# opk-pi-1wire-i2c-v1.net
KiCad netlist of a schematic drawn in EAGLE
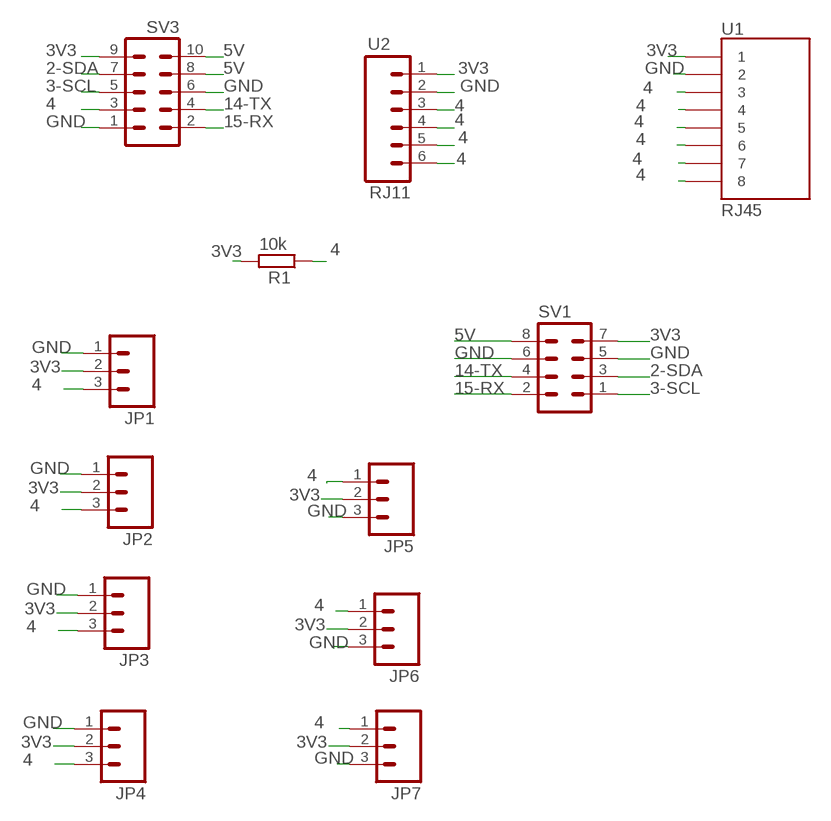
[diagram p0: schematic, sheet 1]

(export (version "E")
  (design (tool "Eeschema 10.0.6"))
  (components
    (comp (ref "JP1")
      (value "M03SCREW")
      (footprint "eagle-import:SCREWTERMINAL-3.5MM-3")
      (libsource (lib "eagle-import") (part "M03SCREW"))
    )
    (comp (ref "JP2")
      (value "M03SCREW")
      (footprint "eagle-import:SCREWTERMINAL-3.5MM-3")
      (libsource (lib "eagle-import") (part "M03SCREW"))
    )
    (comp (ref "JP3")
      (value "M03SCREW")
      (footprint "eagle-import:SCREWTERMINAL-3.5MM-3")
      (libsource (lib "eagle-import") (part "M03SCREW"))
    )
    (comp (ref "JP4")
      (value "M03SCREW")
      (footprint "eagle-import:SCREWTERMINAL-3.5MM-3")
      (libsource (lib "eagle-import") (part "M03SCREW"))
    )
    (comp (ref "JP5")
      (value "M03SCREW")
      (footprint "eagle-import:SCREWTERMINAL-3.5MM-3")
      (libsource (lib "eagle-import") (part "M03SCREW"))
    )
    (comp (ref "JP6")
      (value "M03SCREW")
      (footprint "eagle-import:SCREWTERMINAL-3.5MM-3")
      (libsource (lib "eagle-import") (part "M03SCREW"))
    )
    (comp (ref "JP7")
      (value "M03SCREW")
      (footprint "eagle-import:SCREWTERMINAL-3.5MM-3")
      (libsource (lib "eagle-import") (part "M03SCREW"))
    )
    (comp (ref "R1")
      (value "10k")
      (footprint "eagle-import:0204_7")
      (libsource (lib "eagle-import") (part "R-EU_0204/7"))
    )
    (comp (ref "SV1")
      (value "MA04-2")
      (footprint "eagle-import:MA04-2")
      (libsource (lib "eagle-import") (part "MA04-2"))
    )
    (comp (ref "SV3")
      (value "MA05-2")
      (footprint "eagle-import:MA05-2")
      (libsource (lib "eagle-import") (part "MA05-2"))
    )
    (comp (ref "U1")
      (value "RJ45")
      (footprint "eagle-import:RJ45-8")
      (libsource (lib "eagle-import") (part "RJ45-8PTH"))
    )
    (comp (ref "U2")
      (value "RJ11")
      (footprint "eagle-import:RJ11-6")
      (libsource (lib "eagle-import") (part "RJ11-6PTH"))
    )
  )
  (nets
    (net (code "1") (name "/2-SDA") (class "Default")
      (node (ref "SV1") (pin "3") (pinfunction "3_3") (pintype "passive"))
      (node (ref "SV3") (pin "7") (pinfunction "7_7") (pintype "passive"))
    )
    (net (code "2") (name "/3-SCL") (class "Default")
      (node (ref "SV1") (pin "1") (pinfunction "1_1") (pintype "passive"))
      (node (ref "SV3") (pin "5") (pinfunction "5_5") (pintype "passive"))
    )
    (net (code "3") (name "/3V3") (class "Default")
      (node (ref "JP1") (pin "2") (pinfunction "2_2") (pintype "passive"))
      (node (ref "JP2") (pin "2") (pinfunction "2_2") (pintype "passive"))
      (node (ref "JP3") (pin "2") (pinfunction "2_2") (pintype "passive"))
      (node (ref "JP4") (pin "2") (pinfunction "2_2") (pintype "passive"))
      (node (ref "JP5") (pin "2") (pinfunction "2_2") (pintype "passive"))
      (node (ref "JP6") (pin "2") (pinfunction "2_2") (pintype "passive"))
      (node (ref "JP7") (pin "2") (pinfunction "2_2") (pintype "passive"))
      (node (ref "R1") (pin "2") (pinfunction "2_2") (pintype "passive"))
      (node (ref "SV1") (pin "7") (pinfunction "7_7") (pintype "passive"))
      (node (ref "SV3") (pin "9") (pinfunction "9_9") (pintype "passive"))
      (node (ref "U1") (pin "1") (pinfunction "1_1") (pintype "bidirectional"))
      (node (ref "U2") (pin "1") (pinfunction "1_1") (pintype "passive"))
    )
    (net (code "4") (name "/4") (class "Default")
      (node (ref "JP1") (pin "3") (pinfunction "3_3") (pintype "passive"))
      (node (ref "JP2") (pin "3") (pinfunction "3_3") (pintype "passive"))
      (node (ref "JP3") (pin "3") (pinfunction "3_3") (pintype "passive"))
      (node (ref "JP4") (pin "3") (pinfunction "3_3") (pintype "passive"))
      (node (ref "JP5") (pin "1") (pinfunction "1_1") (pintype "passive"))
      (node (ref "JP6") (pin "1") (pinfunction "1_1") (pintype "passive"))
      (node (ref "JP7") (pin "1") (pinfunction "1_1") (pintype "passive"))
      (node (ref "R1") (pin "1") (pinfunction "1_1") (pintype "passive"))
      (node (ref "SV3") (pin "3") (pinfunction "3_3") (pintype "passive"))
      (node (ref "U1") (pin "3") (pinfunction "3_3") (pintype "bidirectional"))
      (node (ref "U1") (pin "4") (pinfunction "4_4") (pintype "bidirectional"))
      (node (ref "U1") (pin "5") (pinfunction "5_5") (pintype "bidirectional"))
      (node (ref "U1") (pin "6") (pinfunction "6_6") (pintype "bidirectional"))
      (node (ref "U1") (pin "7") (pinfunction "7_7") (pintype "bidirectional"))
      (node (ref "U1") (pin "8") (pinfunction "8_8") (pintype "bidirectional"))
      (node (ref "U2") (pin "3") (pinfunction "3_3") (pintype "passive"))
      (node (ref "U2") (pin "4") (pinfunction "4_4") (pintype "passive"))
      (node (ref "U2") (pin "5") (pinfunction "5_5") (pintype "passive"))
      (node (ref "U2") (pin "6") (pinfunction "6_6") (pintype "passive"))
    )
    (net (code "5") (name "/5V") (class "Default")
      (node (ref "SV1") (pin "8") (pinfunction "8_8") (pintype "passive"))
      (node (ref "SV3") (pin "10") (pinfunction "10_10") (pintype "passive"))
      (node (ref "SV3") (pin "8") (pinfunction "8_8") (pintype "passive"))
    )
    (net (code "6") (name "/14-TX") (class "Default")
      (node (ref "SV1") (pin "4") (pinfunction "4_4") (pintype "passive"))
      (node (ref "SV3") (pin "4") (pinfunction "4_4") (pintype "passive"))
    )
    (net (code "7") (name "/15-RX") (class "Default")
      (node (ref "SV1") (pin "2") (pinfunction "2_2") (pintype "passive"))
      (node (ref "SV3") (pin "2") (pinfunction "2_2") (pintype "passive"))
    )
    (net (code "8") (name "/GND") (class "Default")
      (node (ref "JP1") (pin "1") (pinfunction "1_1") (pintype "passive"))
      (node (ref "JP2") (pin "1") (pinfunction "1_1") (pintype "passive"))
      (node (ref "JP3") (pin "1") (pinfunction "1_1") (pintype "passive"))
      (node (ref "JP4") (pin "1") (pinfunction "1_1") (pintype "passive"))
      (node (ref "JP5") (pin "3") (pinfunction "3_3") (pintype "passive"))
      (node (ref "JP6") (pin "3") (pinfunction "3_3") (pintype "passive"))
      (node (ref "JP7") (pin "3") (pinfunction "3_3") (pintype "passive"))
      (node (ref "SV1") (pin "5") (pinfunction "5_5") (pintype "passive"))
      (node (ref "SV1") (pin "6") (pinfunction "6_6") (pintype "passive"))
      (node (ref "SV3") (pin "1") (pinfunction "1_1") (pintype "passive"))
      (node (ref "SV3") (pin "6") (pinfunction "6_6") (pintype "passive"))
      (node (ref "U1") (pin "2") (pinfunction "2_2") (pintype "bidirectional"))
      (node (ref "U2") (pin "2") (pinfunction "2_2") (pintype "passive"))
    )
  )
)
